# supply.net
KiCad netlist of a schematic drawn in Altium Designer
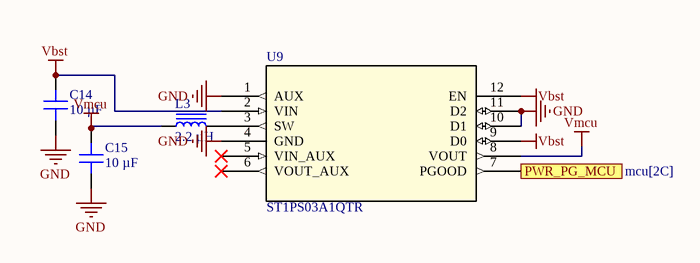
[diagram p0: supply.SchDoc]

(export (version "E")
  (design (tool "Eeschema 10.0.6"))
  (components
    (comp (ref "C14")
      (value "10 µF")
      (footprint "CAP 0402_1005")
      (description "CAP CER 0.1UF 4V X5R 0402")
      (fields (field (name "PART NUMBER") "C0402C104K7PAC7867") (field (name "MANUFACTURER") "KEMET"))
      (libsource (lib "Celestial Altium Library - altium_library") (part "Capacitor"))
    )
    (comp (ref "C15")
      (value "10 µF")
      (footprint "CAP 0402_1005")
      (description "CAP CER 0.1UF 4V X5R 0402")
      (fields (field (name "PART NUMBER") "C0402C104K7PAC7867") (field (name "MANUFACTURER") "KEMET"))
      (libsource (lib "Celestial Altium Library - altium_library") (part "Capacitor"))
    )
    (comp (ref "L3")
      (value "2.2 µH")
      (footprint "TDK VLS201612CX")
      (description "FIXED IND 6.8UH 930MA 368MOHM SM")
      (fields
        (field (name "PART NUMBER") "VLS201612CX-6R8M-1")
        (field (name "MANUFACTURER") "TDK Corporation")
      )
      (libsource (lib "Celestial Altium Library - altium_library") (part "Inductor"))
    )
    (comp (ref "U9")
      (value "ST1PS03A1QTR")
      (footprint "TQFN12_2X1P7_STM")
      (description "No Description Available")
      (libsource (lib "ST1PS03A1QTR") (part "ST1PS03A1QTR"))
    )
  )
  (nets
    (net (code "1") (name "/PWR_PG_MCU") (class "Default")
      (node (ref "U9") (pin "7") (pinfunction "PGOOD_7") (pintype "output"))
    )
    (net (code "2") (name "GND") (class "Default")
      (node (ref "C14") (pin "2") (pinfunction "2_2") (pintype "passive"))
      (node (ref "C15") (pin "2") (pinfunction "2_2") (pintype "passive"))
      (node (ref "U9") (pin "1") (pinfunction "AUX_1") (pintype "output"))
      (node (ref "U9") (pin "10") (pinfunction "D1_10") (pintype "bidirectional"))
      (node (ref "U9") (pin "11") (pinfunction "D2_11") (pintype "bidirectional"))
      (node (ref "U9") (pin "4") (pinfunction "GND_4") (pintype "power_in"))
    )
    (net (code "3") (name "Net-(U9-SW)") (class "Default")
      (node (ref "L3") (pin "2") (pinfunction "2_2") (pintype "passive"))
      (node (ref "U9") (pin "3") (pinfunction "SW_3") (pintype "output"))
    )
    (net (code "4") (name "Vbst") (class "Default")
      (node (ref "C14") (pin "1") (pinfunction "1_1") (pintype "passive"))
      (node (ref "U9") (pin "12") (pinfunction "EN_12") (pintype "passive"))
      (node (ref "U9") (pin "2") (pinfunction "VIN_2") (pintype "input"))
      (node (ref "U9") (pin "9") (pinfunction "D0_9") (pintype "bidirectional"))
    )
    (net (code "5") (name "Vmcu") (class "Default")
      (node (ref "C15") (pin "1") (pinfunction "1_1") (pintype "passive"))
      (node (ref "L3") (pin "1") (pinfunction "1_1") (pintype "passive"))
      (node (ref "U9") (pin "8") (pinfunction "VOUT_8") (pintype "output"))
    )
    (net (code "6") (name "unconnected-(U9-VIN_AUX-Pad5)") (class "Default")
      (node (ref "U9") (pin "5") (pinfunction "VIN_AUX_5") (pintype "input+no_connect"))
    )
    (net (code "7") (name "unconnected-(U9-VOUT_AUX-Pad6)") (class "Default")
      (node (ref "U9") (pin "6") (pinfunction "VOUT_AUX_6") (pintype "output+no_connect"))
    )
  )
)
